# eeZee_tiny.net
KiCad netlist of a schematic drawn in EAGLE
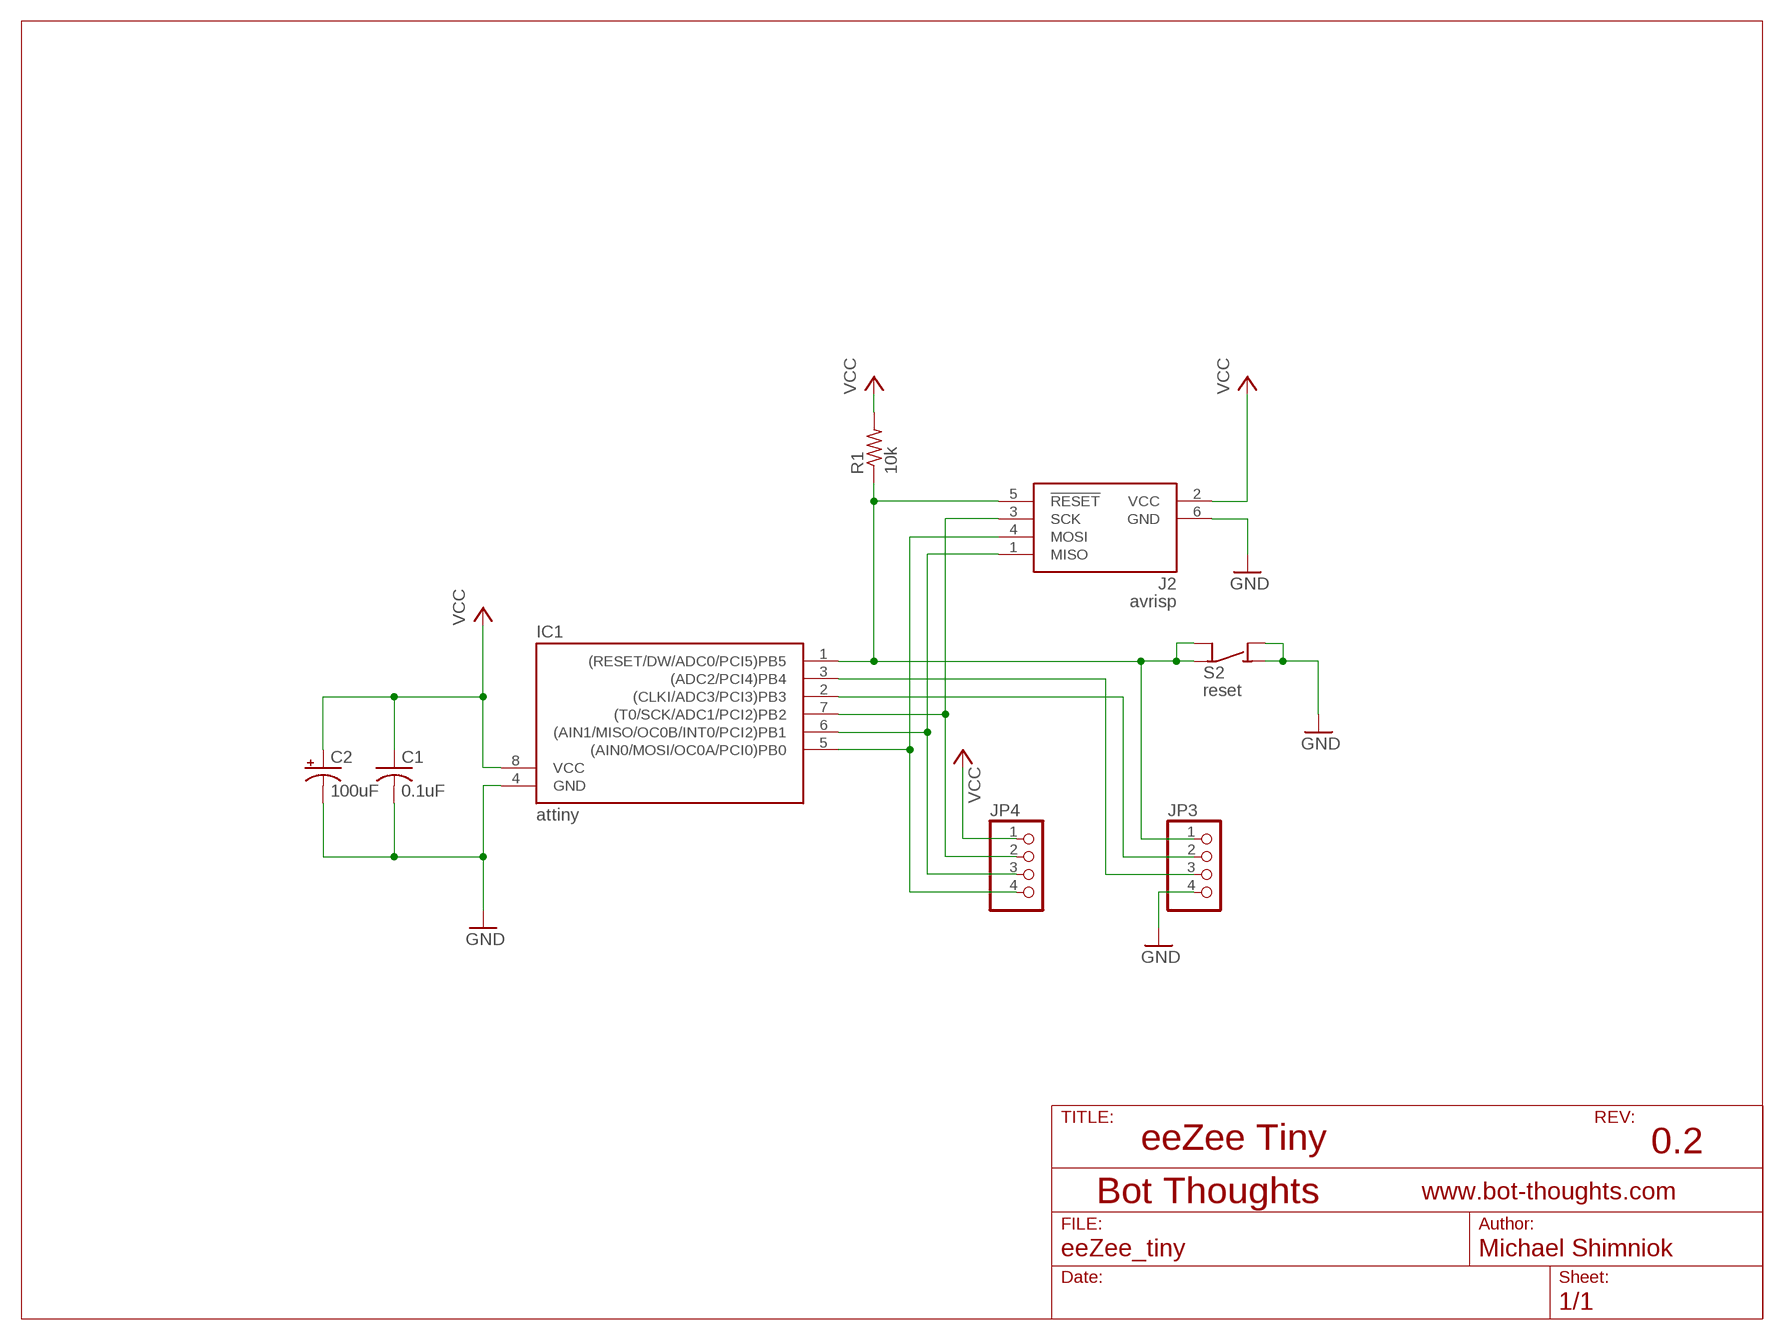
[diagram p0: schematic, sheet 1]

(export (version "E")
  (design (tool "Eeschema 10.0.6"))
  (components
    (comp (ref "C1")
      (value "0.1uF")
      (footprint "eagle-import:C0603")
      (fields (field (name "PARTNO") "0603YC104KAT2A"))
      (libsource (lib "eagle-import") (part "C-USC0603"))
    )
    (comp (ref "C2")
      (value "100uF")
      (footprint "eagle-import:SMC_B")
      (fields (field (name "PARTNO") "F930J107MBA"))
      (libsource (lib "eagle-import") (part "CPOL-USSMCB"))
    )
    (comp (ref "IC1")
      (value "attiny")
      (footprint "eagle-import:DIL08")
      (fields (field (name "PARTNO") "A08-LC-TT-R"))
      (libsource (lib "eagle-import") (part "ATTINY13P-20"))
    )
    (comp (ref "J2")
      (value "avrisp")
      (footprint "eagle-import:CON6P2R")
      (libsource (lib "eagle-import") (part "AVRISP6"))
    )
    (comp (ref "JP3")
      (value "PINHD-1X04_2.54-S")
      (footprint "eagle-import:1X04-S")
      (libsource (lib "eagle-import") (part "PINHD-1X04_2.54-S"))
    )
    (comp (ref "JP4")
      (value "PINHD-1X04_2.54-S")
      (footprint "eagle-import:1X04-S")
      (libsource (lib "eagle-import") (part "PINHD-1X04_2.54-S"))
    )
    (comp (ref "R1")
      (value "10k")
      (footprint "eagle-import:R0603")
      (fields (field (name "PARTNO") "ERJ-3GEYJ103V"))
      (libsource (lib "eagle-import") (part "R-US_R0603"))
    )
    (comp (ref "S2")
      (value "reset")
      (footprint "eagle-import:6MMTACTILE_4PIN")
      (libsource (lib "eagle-import") (part "SPST4"))
    )
  )
  (nets
    (net (code "1") (name "GND") (class "Default")
      (node (ref "C1") (pin "2") (pinfunction "2_2") (pintype "passive"))
      (node (ref "C2") (pin "-") (pinfunction "-_-") (pintype "passive"))
      (node (ref "IC1") (pin "4") (pinfunction "GND_4") (pintype "power_in"))
      (node (ref "J2") (pin "6") (pinfunction "GND_6") (pintype "power_in"))
      (node (ref "JP3") (pin "4") (pinfunction "4_4") (pintype "passive"))
      (node (ref "S2") (pin "A1") (pinfunction "NO_A1") (pintype "passive"))
      (node (ref "S2") (pin "A2") (pinfunction "NO_A2") (pintype "passive"))
    )
    (net (code "2") (name "Net-(IC1-(ADC2{slash}PCI4)PB4)") (class "Default")
      (node (ref "IC1") (pin "3") (pinfunction "(ADC2/PCI4)PB4_3") (pintype "bidirectional"))
      (node (ref "JP3") (pin "3") (pinfunction "3_3") (pintype "passive"))
    )
    (net (code "3") (name "Net-(IC1-(AIN0{slash}MOSI{slash}OC0A{slash}PCI0)PB0)") (class "Default")
      (node (ref "IC1") (pin "5") (pinfunction "(AIN0/MOSI/OC0A/PCI0)PB0_5") (pintype "bidirectional"))
      (node (ref "J2") (pin "4") (pinfunction "MOSI_4") (pintype "output"))
      (node (ref "JP4") (pin "4") (pinfunction "4_4") (pintype "passive"))
    )
    (net (code "4") (name "Net-(IC1-(AIN1{slash}MISO{slash}OC0B{slash}INT0{slash}PCI2)PB1)") (class "Default")
      (node (ref "IC1") (pin "6") (pinfunction "(AIN1/MISO/OC0B/INT0/PCI2)PB1_6") (pintype "bidirectional"))
      (node (ref "J2") (pin "1") (pinfunction "MISO_1") (pintype "input"))
      (node (ref "JP4") (pin "3") (pinfunction "3_3") (pintype "passive"))
    )
    (net (code "5") (name "Net-(IC1-(CLKI{slash}ADC3{slash}PCI3)PB3)") (class "Default")
      (node (ref "IC1") (pin "2") (pinfunction "(CLKI/ADC3/PCI3)PB3_2") (pintype "bidirectional"))
      (node (ref "JP3") (pin "2") (pinfunction "2_2") (pintype "passive"))
    )
    (net (code "6") (name "Net-(IC1-(RESET{slash}DW{slash}ADC0{slash}PCI5)PB5)") (class "Default")
      (node (ref "IC1") (pin "1") (pinfunction "(RESET/DW/ADC0/PCI5)PB5_1") (pintype "bidirectional"))
      (node (ref "J2") (pin "5") (pinfunction "~{RESET}_5") (pintype "output"))
      (node (ref "JP3") (pin "1") (pinfunction "1_1") (pintype "passive"))
      (node (ref "R1") (pin "1") (pinfunction "1_1") (pintype "passive"))
      (node (ref "S2") (pin "B1") (pinfunction "COM_B1") (pintype "passive"))
      (node (ref "S2") (pin "B2") (pinfunction "COM_B2") (pintype "passive"))
    )
    (net (code "7") (name "Net-(IC1-(T0{slash}SCK{slash}ADC1{slash}PCI2)PB2)") (class "Default")
      (node (ref "IC1") (pin "7") (pinfunction "(T0/SCK/ADC1/PCI2)PB2_7") (pintype "bidirectional"))
      (node (ref "J2") (pin "3") (pinfunction "SCK_3") (pintype "output"))
      (node (ref "JP4") (pin "2") (pinfunction "2_2") (pintype "passive"))
    )
    (net (code "8") (name "VCC") (class "Default")
      (node (ref "C1") (pin "1") (pinfunction "1_1") (pintype "passive"))
      (node (ref "C2") (pin "+") (pinfunction "+_+") (pintype "passive"))
      (node (ref "IC1") (pin "8") (pinfunction "VCC_8") (pintype "power_in"))
      (node (ref "J2") (pin "2") (pinfunction "VCC_2") (pintype "power_in"))
      (node (ref "JP4") (pin "1") (pinfunction "1_1") (pintype "passive"))
      (node (ref "R1") (pin "2") (pinfunction "2_2") (pintype "passive"))
    )
  )
)
